# doan2.net
KiCad netlist of a schematic drawn in Altium Designer
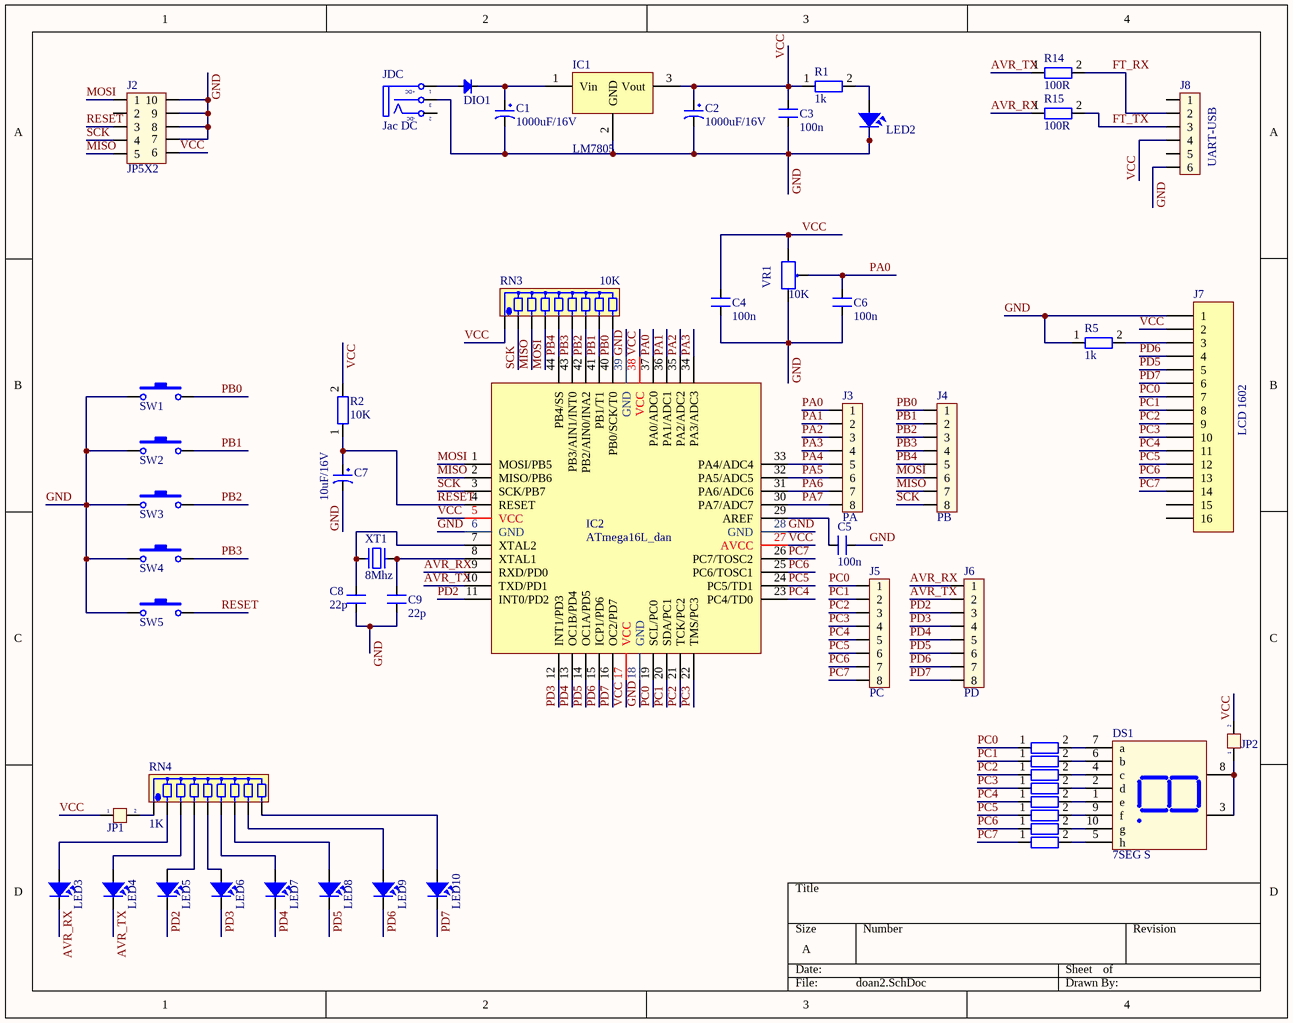
[diagram p0: doan2.SchDoc]

(export (version "E")
  (design (tool "Eeschema 10.0.6"))
  (components
    (comp (ref "C1")
      (value "1000uF/16V")
      (footprint "CAP1000uf/25V")
      (description "Cap 1000uF/16V - 220uF/50V")
      (libsource (lib "doan2") (part "CAP1000uf/25V"))
    )
    (comp (ref "C2")
      (value "1000uF/16V")
      (footprint "CAP1000uf/25V")
      (description "Cap 1000uF/16V - 220uF/50V")
      (libsource (lib "doan2") (part "CAP1000uf/25V"))
    )
    (comp (ref "C3")
      (value "100n")
      (footprint "SM-CAP-0805")
      (fields (field (name "DESIGNED BY") "VanDungEvn"))
      (libsource (lib "doan2") (part "CN"))
    )
    (comp (ref "C4")
      (value "100n")
      (footprint "SM-CAP-0805")
      (fields (field (name "DESIGNED BY") "VanDungEvn"))
      (libsource (lib "doan2") (part "CN"))
    )
    (comp (ref "C5")
      (value "100n")
      (footprint "SM-CAP-0805")
      (fields (field (name "DESIGNED BY") "VanDungEvn"))
      (libsource (lib "doan2") (part "CN"))
    )
    (comp (ref "C6")
      (value "100n")
      (footprint "SM-CAP-0805")
      (fields (field (name "DESIGNED BY") "VanDungEvn"))
      (libsource (lib "doan2") (part "CN"))
    )
    (comp (ref "C7")
      (value "10uF/16V")
      (footprint "CAP10uf/16V")
      (description "Cap 1000uF/16V - 220uF/50V")
      (libsource (lib "doan2") (part "CAP10uf/16V"))
    )
    (comp (ref "C8")
      (value "22p")
      (footprint "SM-CAP-0805")
      (fields (field (name "DESIGNED BY") "VanDungEvn"))
      (libsource (lib "doan2") (part "CN"))
    )
    (comp (ref "C9")
      (value "22p")
      (footprint "SM-CAP-0805")
      (fields (field (name "DESIGNED BY") "VanDungEvn"))
      (libsource (lib "doan2") (part "CN"))
    )
    (comp (ref "DIO1")
      (value "Diode")
      (footprint "DIO-SMD-106")
      (description "Default Diode")
      (fields (field (name "PUBLISHER") "Altium Limited"))
      (libsource (lib "doan2") (part "Diode"))
    )
    (comp (ref "DS1")
      (value "7SEG S")
      (footprint "7SEGS")
      (description "Single 7 Seg Dipslay")
      (libsource (lib "doan2") (part "LED7S"))
    )
    (comp (ref "IC1") (value "LM7805") (footprint "LM7805/DPAK") (libsource (lib "doan2") (part "LM7805")))
    (comp (ref "IC2")
      (value "ATmega16L_dan")
      (footprint "DIP44/W0.6")
      (libsource (lib "doan2") (part "ATmega16L_dan"))
    )
    (comp (ref "J2") (value "JP5X2") (footprint "JP5X2") (libsource (lib "doan2") (part "JP5X2")))
    (comp (ref "J3")
      (value "PA")
      (footprint "JP8")
      (description "JP8 PIN")
      (libsource (lib "doan2") (part "JP8"))
    )
    (comp (ref "J4")
      (value "PB")
      (footprint "JP8")
      (description "JP8 PIN")
      (libsource (lib "doan2") (part "JP8"))
    )
    (comp (ref "J5")
      (value "PC")
      (footprint "JP8")
      (description "JP8 PIN")
      (libsource (lib "doan2") (part "JP8"))
    )
    (comp (ref "J6")
      (value "PD")
      (footprint "JP8")
      (description "JP8 PIN")
      (libsource (lib "doan2") (part "JP8"))
    )
    (comp (ref "J7")
      (value "LCD 1602")
      (footprint "JP16-C1T")
      (description "WR-PHD 2.54 mm Angled Socket Header")
      (fields
        (field (name "MANUFACTURER") "Würth Elektronik eiSos GmbH")
        (field (name "PARTNO") "613016143121")
        (field (name "CREATED BY") "Karrer Zheng")
      )
      (libsource (lib "doan2") (part "JP16"))
    )
    (comp (ref "J8")
      (value "UART-USB")
      (footprint "JP6")
      (description "JP6 PIN")
      (libsource (lib "doan2") (part "JP6"))
    )
    (comp (ref "JDC")
      (value "Jac DC")
      (footprint "DC-IN")
      (description "Jac DC input")
      (libsource (lib "doan2") (part "DCIN"))
    )
    (comp (ref "JP1") (value "Jumper 2") (footprint "JP2") (libsource (lib "doan2") (part "JP 2")))
    (comp (ref "JP2") (value "Jumper 2") (footprint "JP2") (libsource (lib "") (part "JP 2_1")))
    (comp (ref "LED2")
      (value "LED SMD")
      (footprint "SM-LED-0805-Green - duplicate")
      (libsource (lib "doan2") (part "LED-SMD-0805"))
    )
    (comp (ref "LED3")
      (value "LED SMD")
      (footprint "SM-LED-0805-Green - duplicate")
      (libsource (lib "doan2") (part "LED-SMD-0805"))
    )
    (comp (ref "LED4")
      (value "LED SMD")
      (footprint "SM-LED-0805-Green - duplicate")
      (libsource (lib "doan2") (part "LED-SMD-0805"))
    )
    (comp (ref "LED5")
      (value "LED SMD")
      (footprint "SM-LED-0805-Green - duplicate")
      (libsource (lib "doan2") (part "LED-SMD-0805"))
    )
    (comp (ref "LED6")
      (value "LED SMD")
      (footprint "SM-LED-0805-Green - duplicate")
      (libsource (lib "doan2") (part "LED-SMD-0805"))
    )
    (comp (ref "LED7")
      (value "LED SMD")
      (footprint "SM-LED-0805-Green - duplicate")
      (libsource (lib "doan2") (part "LED-SMD-0805"))
    )
    (comp (ref "LED8")
      (value "LED SMD")
      (footprint "SM-LED-0805-Green - duplicate")
      (libsource (lib "doan2") (part "LED-SMD-0805"))
    )
    (comp (ref "LED9")
      (value "LED SMD")
      (footprint "SM-LED-0805-Green - duplicate")
      (libsource (lib "doan2") (part "LED-SMD-0805"))
    )
    (comp (ref "LED10")
      (value "LED SMD")
      (footprint "SM-LED-0805-Green - duplicate")
      (libsource (lib "doan2") (part "LED-SMD-0805"))
    )
    (comp (ref "R1")
      (value "1k")
      (footprint "SM-RES-0805")
      (description "Resistor 1/4W")
      (libsource (lib "doan2") (part "R1/4W"))
    )
    (comp (ref "R2")
      (value "10K")
      (footprint "SM-RES-0805")
      (description "Resistor 1/4W")
      (libsource (lib "doan2") (part "R1/4W"))
    )
    (comp (ref "R5")
      (value "1k")
      (footprint "SM-RES-0805")
      (description "Resistor 1/4W")
      (libsource (lib "doan2") (part "R1/4W"))
    )
    (comp (ref "R6")
      (value "1k")
      (footprint "SM-RES-0805")
      (description "Resistor 1/4W")
      (libsource (lib "doan2") (part "R1/4W"))
    )
    (comp (ref "R7")
      (value "1k")
      (footprint "SM-RES-0805")
      (description "Resistor 1/4W")
      (libsource (lib "doan2") (part "R1/4W"))
    )
    (comp (ref "R8")
      (value "1k")
      (footprint "SM-RES-0805")
      (description "Resistor 1/4W")
      (libsource (lib "doan2") (part "R1/4W"))
    )
    (comp (ref "R9")
      (value "1k")
      (footprint "SM-RES-0805")
      (description "Resistor 1/4W")
      (libsource (lib "doan2") (part "R1/4W"))
    )
    (comp (ref "R10")
      (value "1k")
      (footprint "SM-RES-0805")
      (description "Resistor 1/4W")
      (libsource (lib "doan2") (part "R1/4W"))
    )
    (comp (ref "R11")
      (value "1k")
      (footprint "SM-RES-0805")
      (description "Resistor 1/4W")
      (libsource (lib "doan2") (part "R1/4W"))
    )
    (comp (ref "R12")
      (value "1k")
      (footprint "SM-RES-0805")
      (description "Resistor 1/4W")
      (libsource (lib "doan2") (part "R1/4W"))
    )
    (comp (ref "R13")
      (value "1k")
      (footprint "SM-RES-0805")
      (description "Resistor 1/4W")
      (libsource (lib "doan2") (part "R1/4W"))
    )
    (comp (ref "R14")
      (value "100R")
      (footprint "SM-RES-0805")
      (description "Resistor 1/4W")
      (libsource (lib "doan2") (part "R1/4W"))
    )
    (comp (ref "R15")
      (value "100R")
      (footprint "SM-RES-0805")
      (description "Resistor 1/4W")
      (libsource (lib "doan2") (part "R1/4W"))
    )
    (comp (ref "RN3")
      (value "10K")
      (footprint "RN8")
      (description "Resistor 8 (Thanh)")
      (libsource (lib "doan2") (part "RN8"))
    )
    (comp (ref "RN4")
      (value "1K")
      (footprint "RN8")
      (description "Resistor 8 (Thanh)")
      (libsource (lib "doan2") (part "RN8"))
    )
    (comp (ref "SW1")
      (value "SW-SMD")
      (footprint "SW-SMD")
      (description "Switch")
      (fields (field (name "PUBLISHER") "Altium Limited"))
      (libsource (lib "doan2") (part "SW-SMD"))
    )
    (comp (ref "SW2")
      (value "SW-SMD")
      (footprint "SW-SMD")
      (description "Switch")
      (fields (field (name "PUBLISHER") "Altium Limited"))
      (libsource (lib "doan2") (part "SW-SMD"))
    )
    (comp (ref "SW3")
      (value "SW-SMD")
      (footprint "SW-SMD")
      (description "Switch")
      (fields (field (name "PUBLISHER") "Altium Limited"))
      (libsource (lib "doan2") (part "SW-SMD"))
    )
    (comp (ref "SW4")
      (value "SW-SMD")
      (footprint "SW-SMD")
      (description "Switch")
      (fields (field (name "PUBLISHER") "Altium Limited"))
      (libsource (lib "doan2") (part "SW-SMD"))
    )
    (comp (ref "SW5")
      (value "RESET")
      (footprint "SW-SMD")
      (description "Switch")
      (fields (field (name "PUBLISHER") "Altium Limited"))
      (libsource (lib "doan2") (part "SW-SMD"))
    )
    (comp (ref "VR1")
      (value "10K")
      (footprint "VR")
      (description "Var Resistor")
      (libsource (lib "doan2") (part "VR"))
    )
    (comp (ref "XT1")
      (value "8Mhz")
      (footprint "XT2")
      (description "Crystal For all Crystal 2pin.")
      (libsource (lib "doan2") (part "XT2"))
    )
  )
  (nets
    (net (code "1") (name "/AVR_RX") (class "Default")
      (node (ref "IC2") (pin "9") (pinfunction "RXD/PD0_9") (pintype "passive"))
      (node (ref "J6") (pin "1") (pinfunction "1_1") (pintype "passive"))
      (node (ref "LED3") (pin "2") (pinfunction "2_2") (pintype "passive"))
      (node (ref "R15") (pin "1") (pinfunction "1_1") (pintype "passive"))
    )
    (net (code "2") (name "/AVR_TX") (class "Default")
      (node (ref "IC2") (pin "10") (pinfunction "TXD/PD1_10") (pintype "passive"))
      (node (ref "J6") (pin "2") (pinfunction "2_2") (pintype "passive"))
      (node (ref "LED4") (pin "2") (pinfunction "2_2") (pintype "passive"))
      (node (ref "R14") (pin "1") (pinfunction "1_1") (pintype "passive"))
    )
    (net (code "3") (name "/FT_RX") (class "Default")
      (node (ref "J8") (pin "2") (pinfunction "2_2") (pintype "passive"))
      (node (ref "R14") (pin "2") (pinfunction "2_2") (pintype "passive"))
    )
    (net (code "4") (name "/FT_TX") (class "Default")
      (node (ref "J8") (pin "3") (pinfunction "3_3") (pintype "passive"))
      (node (ref "R15") (pin "2") (pinfunction "2_2") (pintype "passive"))
    )
    (net (code "5") (name "/GND") (class "Default")
      (node (ref "C1") (pin "2") (pinfunction "2_2") (pintype "passive"))
      (node (ref "C2") (pin "2") (pinfunction "2_2") (pintype "passive"))
      (node (ref "C3") (pin "1") (pinfunction "1_1") (pintype "passive"))
      (node (ref "C4") (pin "1") (pinfunction "1_1") (pintype "passive"))
      (node (ref "C5") (pin "1") (pinfunction "1_1") (pintype "passive"))
      (node (ref "C6") (pin "1") (pinfunction "1_1") (pintype "passive"))
      (node (ref "C7") (pin "2") (pinfunction "2_2") (pintype "passive"))
      (node (ref "C8") (pin "1") (pinfunction "1_1") (pintype "passive"))
      (node (ref "C9") (pin "1") (pinfunction "1_1") (pintype "passive"))
      (node (ref "IC1") (pin "2") (pinfunction "GND_2") (pintype "passive"))
      (node (ref "IC2") (pin "18") (pinfunction "GND_18") (pintype "passive"))
      (node (ref "IC2") (pin "28") (pinfunction "GND_28") (pintype "passive"))
      (node (ref "IC2") (pin "39") (pinfunction "GND_39") (pintype "passive"))
      (node (ref "IC2") (pin "6") (pinfunction "GND_6") (pintype "passive"))
      (node (ref "J2") (pin "10") (pinfunction "10_10") (pintype "passive"))
      (node (ref "J2") (pin "7") (pinfunction "7_7") (pintype "passive"))
      (node (ref "J2") (pin "8") (pinfunction "8_8") (pintype "passive"))
      (node (ref "J2") (pin "9") (pinfunction "9_9") (pintype "passive"))
      (node (ref "J7") (pin "1") (pinfunction "1_1") (pintype "passive"))
      (node (ref "J8") (pin "6") (pinfunction "6_6") (pintype "passive"))
      (node (ref "JDC") (pin "3") (pinfunction "S_3") (pintype "power_in"))
      (node (ref "LED2") (pin "2") (pinfunction "2_2") (pintype "passive"))
      (node (ref "R5") (pin "1") (pinfunction "1_1") (pintype "passive"))
      (node (ref "SW1") (pin "1") (pinfunction "1_1") (pintype "passive"))
      (node (ref "SW2") (pin "1") (pinfunction "1_1") (pintype "passive"))
      (node (ref "SW3") (pin "1") (pinfunction "1_1") (pintype "passive"))
      (node (ref "SW4") (pin "1") (pinfunction "1_1") (pintype "passive"))
      (node (ref "SW5") (pin "1") (pinfunction "1_1") (pintype "passive"))
      (node (ref "VR1") (pin "3") (pinfunction "3_3") (pintype "passive"))
    )
    (net (code "6") (name "/MISO") (class "Default")
      (node (ref "IC2") (pin "2") (pinfunction "MISO/PB6_2") (pintype "passive"))
      (node (ref "J2") (pin "5") (pinfunction "5_5") (pintype "passive"))
      (node (ref "J4") (pin "7") (pinfunction "7_7") (pintype "passive"))
      (node (ref "RN3") (pin "3") (pinfunction "3_3") (pintype "passive"))
    )
    (net (code "7") (name "/MOSI") (class "Default")
      (node (ref "IC2") (pin "1") (pinfunction "MOSI/PB5_1") (pintype "passive"))
      (node (ref "J2") (pin "1") (pinfunction "1_1") (pintype "passive"))
      (node (ref "J4") (pin "6") (pinfunction "6_6") (pintype "passive"))
      (node (ref "RN3") (pin "4") (pinfunction "4_4") (pintype "passive"))
    )
    (net (code "8") (name "/PA0") (class "Default")
      (node (ref "C6") (pin "2") (pinfunction "2_2") (pintype "passive"))
      (node (ref "IC2") (pin "37") (pinfunction "PA0/ADC0_37") (pintype "passive"))
      (node (ref "J3") (pin "1") (pinfunction "1_1") (pintype "passive"))
      (node (ref "VR1") (pin "2") (pinfunction "2_2") (pintype "passive"))
    )
    (net (code "9") (name "/PA1") (class "Default")
      (node (ref "IC2") (pin "36") (pinfunction "PA1/ADC1_36") (pintype "passive"))
      (node (ref "J3") (pin "2") (pinfunction "2_2") (pintype "passive"))
    )
    (net (code "10") (name "/PA2") (class "Default")
      (node (ref "IC2") (pin "35") (pinfunction "PA2/ADC2_35") (pintype "passive"))
      (node (ref "J3") (pin "3") (pinfunction "3_3") (pintype "passive"))
    )
    (net (code "11") (name "/PA3") (class "Default")
      (node (ref "IC2") (pin "34") (pinfunction "PA3/ADC3_34") (pintype "passive"))
      (node (ref "J3") (pin "4") (pinfunction "4_4") (pintype "passive"))
    )
    (net (code "12") (name "/PA4") (class "Default")
      (node (ref "IC2") (pin "33") (pinfunction "PA4/ADC4_33") (pintype "passive"))
      (node (ref "J3") (pin "5") (pinfunction "5_5") (pintype "passive"))
    )
    (net (code "13") (name "/PA5") (class "Default")
      (node (ref "IC2") (pin "32") (pinfunction "PA5/ADC5_32") (pintype "passive"))
      (node (ref "J3") (pin "6") (pinfunction "6_6") (pintype "passive"))
    )
    (net (code "14") (name "/PA6") (class "Default")
      (node (ref "IC2") (pin "31") (pinfunction "PA6/ADC6_31") (pintype "passive"))
      (node (ref "J3") (pin "7") (pinfunction "7_7") (pintype "passive"))
    )
    (net (code "15") (name "/PA7") (class "Default")
      (node (ref "IC2") (pin "30") (pinfunction "PA7/ADC7_30") (pintype "passive"))
      (node (ref "J3") (pin "8") (pinfunction "8_8") (pintype "passive"))
    )
    (net (code "16") (name "/PB0") (class "Default")
      (node (ref "IC2") (pin "40") (pinfunction "PB0/SCK/T0_40") (pintype "passive"))
      (node (ref "J4") (pin "1") (pinfunction "1_1") (pintype "passive"))
      (node (ref "RN3") (pin "9") (pinfunction "9_9") (pintype "passive"))
      (node (ref "SW1") (pin "2") (pinfunction "2_2") (pintype "passive"))
    )
    (net (code "17") (name "/PB1") (class "Default")
      (node (ref "IC2") (pin "41") (pinfunction "PB1/T1_41") (pintype "passive"))
      (node (ref "J4") (pin "2") (pinfunction "2_2") (pintype "passive"))
      (node (ref "RN3") (pin "8") (pinfunction "8_8") (pintype "passive"))
      (node (ref "SW2") (pin "2") (pinfunction "2_2") (pintype "passive"))
    )
    (net (code "18") (name "/PB2") (class "Default")
      (node (ref "IC2") (pin "42") (pinfunction "PB2/AIN0/INA2_42") (pintype "passive"))
      (node (ref "J4") (pin "3") (pinfunction "3_3") (pintype "passive"))
      (node (ref "RN3") (pin "7") (pinfunction "7_7") (pintype "passive"))
      (node (ref "SW3") (pin "2") (pinfunction "2_2") (pintype "passive"))
    )
    (net (code "19") (name "/PB3") (class "Default")
      (node (ref "IC2") (pin "43") (pinfunction "PB3/AIN1/INT0_43") (pintype "passive"))
      (node (ref "J4") (pin "4") (pinfunction "4_4") (pintype "passive"))
      (node (ref "RN3") (pin "6") (pinfunction "6_6") (pintype "passive"))
      (node (ref "SW4") (pin "2") (pinfunction "2_2") (pintype "passive"))
    )
    (net (code "20") (name "/PB4") (class "Default")
      (node (ref "IC2") (pin "44") (pinfunction "PB4/SS_44") (pintype "passive"))
      (node (ref "J4") (pin "5") (pinfunction "5_5") (pintype "passive"))
      (node (ref "RN3") (pin "5") (pinfunction "5_5") (pintype "passive"))
    )
    (net (code "21") (name "/PC0") (class "Default")
      (node (ref "IC2") (pin "19") (pinfunction "SCL/PC0_19") (pintype "passive"))
      (node (ref "J5") (pin "1") (pinfunction "1_1") (pintype "passive"))
      (node (ref "J7") (pin "7") (pinfunction "7_7") (pintype "passive"))
      (node (ref "R6") (pin "1") (pinfunction "1_1") (pintype "passive"))
    )
    (net (code "22") (name "/PC1") (class "Default")
      (node (ref "IC2") (pin "20") (pinfunction "SDA/PC1_20") (pintype "passive"))
      (node (ref "J5") (pin "2") (pinfunction "2_2") (pintype "passive"))
      (node (ref "J7") (pin "8") (pinfunction "8_8") (pintype "passive"))
      (node (ref "R7") (pin "1") (pinfunction "1_1") (pintype "passive"))
    )
    (net (code "23") (name "/PC2") (class "Default")
      (node (ref "IC2") (pin "21") (pinfunction "TCK/PC2_21") (pintype "passive"))
      (node (ref "J5") (pin "3") (pinfunction "3_3") (pintype "passive"))
      (node (ref "J7") (pin "9") (pinfunction "9_9") (pintype "passive"))
      (node (ref "R8") (pin "1") (pinfunction "1_1") (pintype "passive"))
    )
    (net (code "24") (name "/PC3") (class "Default")
      (node (ref "IC2") (pin "22") (pinfunction "TMS/PC3_22") (pintype "passive"))
      (node (ref "J5") (pin "4") (pinfunction "4_4") (pintype "passive"))
      (node (ref "J7") (pin "10") (pinfunction "10_10") (pintype "passive"))
      (node (ref "R9") (pin "1") (pinfunction "1_1") (pintype "passive"))
    )
    (net (code "25") (name "/PC4") (class "Default")
      (node (ref "IC2") (pin "23") (pinfunction "PC4/TD0_23") (pintype "passive"))
      (node (ref "J5") (pin "5") (pinfunction "5_5") (pintype "passive"))
      (node (ref "J7") (pin "11") (pinfunction "11_11") (pintype "passive"))
      (node (ref "R10") (pin "1") (pinfunction "1_1") (pintype "passive"))
    )
    (net (code "26") (name "/PC5") (class "Default")
      (node (ref "IC2") (pin "24") (pinfunction "PC5/TD1_24") (pintype "passive"))
      (node (ref "J5") (pin "6") (pinfunction "6_6") (pintype "passive"))
      (node (ref "J7") (pin "12") (pinfunction "12_12") (pintype "passive"))
      (node (ref "R11") (pin "1") (pinfunction "1_1") (pintype "passive"))
    )
    (net (code "27") (name "/PC6") (class "Default")
      (node (ref "IC2") (pin "25") (pinfunction "PC6/TOSC1_25") (pintype "passive"))
      (node (ref "J5") (pin "7") (pinfunction "7_7") (pintype "passive"))
      (node (ref "J7") (pin "13") (pinfunction "13_13") (pintype "passive"))
      (node (ref "R12") (pin "1") (pinfunction "1_1") (pintype "passive"))
    )
    (net (code "28") (name "/PC7") (class "Default")
      (node (ref "IC2") (pin "26") (pinfunction "PC7/TOSC2_26") (pintype "passive"))
      (node (ref "J5") (pin "8") (pinfunction "8_8") (pintype "passive"))
      (node (ref "J7") (pin "14") (pinfunction "14_14") (pintype "passive"))
      (node (ref "R13") (pin "1") (pinfunction "1_1") (pintype "passive"))
    )
    (net (code "29") (name "/PD2") (class "Default")
      (node (ref "IC2") (pin "11") (pinfunction "INT0/PD2_11") (pintype "passive"))
      (node (ref "J6") (pin "3") (pinfunction "3_3") (pintype "passive"))
      (node (ref "LED5") (pin "2") (pinfunction "2_2") (pintype "passive"))
    )
    (net (code "30") (name "/PD3") (class "Default")
      (node (ref "IC2") (pin "12") (pinfunction "INT1/PD3_12") (pintype "passive"))
      (node (ref "J6") (pin "4") (pinfunction "4_4") (pintype "passive"))
      (node (ref "LED6") (pin "2") (pinfunction "2_2") (pintype "passive"))
    )
    (net (code "31") (name "/PD4") (class "Default")
      (node (ref "IC2") (pin "13") (pinfunction "OC1B/PD4_13") (pintype "passive"))
      (node (ref "J6") (pin "5") (pinfunction "5_5") (pintype "passive"))
      (node (ref "LED7") (pin "2") (pinfunction "2_2") (pintype "passive"))
    )
    (net (code "32") (name "/PD5") (class "Default")
      (node (ref "IC2") (pin "14") (pinfunction "OC1A/PD5_14") (pintype "passive"))
      (node (ref "J6") (pin "6") (pinfunction "6_6") (pintype "passive"))
      (node (ref "J7") (pin "5") (pinfunction "5_5") (pintype "passive"))
      (node (ref "LED8") (pin "2") (pinfunction "2_2") (pintype "passive"))
    )
    (net (code "33") (name "/PD6") (class "Default")
      (node (ref "IC2") (pin "15") (pinfunction "ICP1/PD6_15") (pintype "passive"))
      (node (ref "J6") (pin "7") (pinfunction "7_7") (pintype "passive"))
      (node (ref "J7") (pin "4") (pinfunction "4_4") (pintype "passive"))
      (node (ref "LED9") (pin "2") (pinfunction "2_2") (pintype "passive"))
    )
    (net (code "34") (name "/PD7") (class "Default")
      (node (ref "IC2") (pin "16") (pinfunction "OC2/PD7_16") (pintype "passive"))
      (node (ref "J6") (pin "8") (pinfunction "8_8") (pintype "passive"))
      (node (ref "J7") (pin "6") (pinfunction "6_6") (pintype "passive"))
      (node (ref "LED10") (pin "2") (pinfunction "2_2") (pintype "passive"))
    )
    (net (code "35") (name "/RESET") (class "Default")
      (node (ref "C7") (pin "1") (pinfunction "1_1") (pintype "passive"))
      (node (ref "IC2") (pin "4") (pinfunction "RESET_4") (pintype "passive"))
      (node (ref "J2") (pin "3") (pinfunction "3_3") (pintype "passive"))
      (node (ref "R2") (pin "1") (pinfunction "1_1") (pintype "passive"))
      (node (ref "SW5") (pin "2") (pinfunction "2_2") (pintype "passive"))
    )
    (net (code "36") (name "/SCK") (class "Default")
      (node (ref "IC2") (pin "3") (pinfunction "SCK/PB7_3") (pintype "passive"))
      (node (ref "J2") (pin "4") (pinfunction "4_4") (pintype "passive"))
      (node (ref "J4") (pin "8") (pinfunction "8_8") (pintype "passive"))
      (node (ref "RN3") (pin "2") (pinfunction "2_2") (pintype "passive"))
    )
    (net (code "37") (name "/VCC") (class "Default")
      (node (ref "C2") (pin "1") (pinfunction "1_1") (pintype "passive"))
      (node (ref "C3") (pin "2") (pinfunction "2_2") (pintype "passive"))
      (node (ref "C4") (pin "2") (pinfunction "2_2") (pintype "passive"))
      (node (ref "IC1") (pin "3") (pinfunction "Vout_3") (pintype "passive"))
      (node (ref "IC2") (pin "17") (pinfunction "VCC_17") (pintype "passive"))
      (node (ref "IC2") (pin "27") (pinfunction "AVCC_27") (pintype "passive"))
      (node (ref "IC2") (pin "38") (pinfunction "VCC_38") (pintype "passive"))
      (node (ref "IC2") (pin "5") (pinfunction "VCC_5") (pintype "passive"))
      (node (ref "J2") (pin "6") (pinfunction "6_6") (pintype "passive"))
      (node (ref "J7") (pin "2") (pinfunction "2_2") (pintype "passive"))
      (node (ref "J8") (pin "4") (pinfunction "4_4") (pintype "passive"))
      (node (ref "JP1") (pin "1") (pinfunction "1_1") (pintype "passive"))
      (node (ref "JP2") (pin "2") (pinfunction "2_2") (pintype "passive"))
      (node (ref "R1") (pin "1") (pinfunction "1_1") (pintype "passive"))
      (node (ref "R2") (pin "2") (pinfunction "2_2") (pintype "passive"))
      (node (ref "RN3") (pin "1") (pinfunction "1_1") (pintype "passive"))
      (node (ref "VR1") (pin "1") (pinfunction "1_1") (pintype "passive"))
    )
    (net (code "38") (name "Net-(DIO1-A)") (class "Default")
      (node (ref "DIO1") (pin "1") (pinfunction "A_1") (pintype "passive"))
      (node (ref "JDC") (pin "1") (pinfunction "T_1") (pintype "passive"))
    )
    (net (code "39") (name "Net-(DIO1-K)") (class "Default")
      (node (ref "C1") (pin "1") (pinfunction "1_1") (pintype "passive"))
      (node (ref "DIO1") (pin "2") (pinfunction "K_2") (pintype "passive"))
      (node (ref "IC1") (pin "1") (pinfunction "Vin_1") (pintype "passive"))
    )
    (net (code "40") (name "Net-(DS1-Vcc-Pad3)") (class "Default")
      (node (ref "DS1") (pin "3") (pinfunction "Vcc_3") (pintype "passive"))
      (node (ref "DS1") (pin "8") (pinfunction "Vcc_8") (pintype "passive"))
      (node (ref "JP2") (pin "1") (pinfunction "1_1") (pintype "passive"))
    )
    (net (code "41") (name "Net-(DS1-a)") (class "Default")
      (node (ref "DS1") (pin "7") (pinfunction "a_7") (pintype "passive"))
      (node (ref "R6") (pin "2") (pinfunction "2_2") (pintype "passive"))
    )
    (net (code "42") (name "Net-(DS1-b)") (class "Default")
      (node (ref "DS1") (pin "6") (pinfunction "b_6") (pintype "passive"))
      (node (ref "R7") (pin "2") (pinfunction "2_2") (pintype "passive"))
    )
    (net (code "43") (name "Net-(DS1-c)") (class "Default")
      (node (ref "DS1") (pin "4") (pinfunction "c_4") (pintype "passive"))
      (node (ref "R8") (pin "2") (pinfunction "2_2") (pintype "passive"))
    )
    (net (code "44") (name "Net-(DS1-d)") (class "Default")
      (node (ref "DS1") (pin "2") (pinfunction "d_2") (pintype "passive"))
      (node (ref "R9") (pin "2") (pinfunction "2_2") (pintype "passive"))
    )
    (net (code "45") (name "Net-(DS1-e)") (class "Default")
      (node (ref "DS1") (pin "1") (pinfunction "e_1") (pintype "passive"))
      (node (ref "R10") (pin "2") (pinfunction "2_2") (pintype "passive"))
    )
    (net (code "46") (name "Net-(DS1-f)") (class "Default")
      (node (ref "DS1") (pin "9") (pinfunction "f_9") (pintype "passive"))
      (node (ref "R11") (pin "2") (pinfunction "2_2") (pintype "passive"))
    )
    (net (code "47") (name "Net-(DS1-g)") (class "Default")
      (node (ref "DS1") (pin "10") (pinfunction "g_10") (pintype "passive"))
      (node (ref "R12") (pin "2") (pinfunction "2_2") (pintype "passive"))
    )
    (net (code "48") (name "Net-(DS1-h)") (class "Default")
      (node (ref "DS1") (pin "5") (pinfunction "h_5") (pintype "passive"))
      (node (ref "R13") (pin "2") (pinfunction "2_2") (pintype "passive"))
    )
    (net (code "49") (name "Net-(IC2-AREF)") (class "Default")
      (node (ref "C5") (pin "2") (pinfunction "2_2") (pintype "passive"))
      (node (ref "IC2") (pin "29") (pinfunction "AREF_29") (pintype "passive"))
    )
    (net (code "50") (name "Net-(IC2-XTAL1)") (class "Default")
      (node (ref "C9") (pin "2") (pinfunction "2_2") (pintype "passive"))
      (node (ref "IC2") (pin "8") (pinfunction "XTAL1_8") (pintype "passive"))
      (node (ref "XT1") (pin "1") (pinfunction "1_1") (pintype "passive"))
    )
    (net (code "51") (name "Net-(IC2-XTAL2)") (class "Default")
      (node (ref "C8") (pin "2") (pinfunction "2_2") (pintype "passive"))
      (node (ref "IC2") (pin "7") (pinfunction "XTAL2_7") (pintype "passive"))
      (node (ref "XT1") (pin "2") (pinfunction "2_2") (pintype "passive"))
    )
    (net (code "52") (name "Net-(J7-Pad3)") (class "Default")
      (node (ref "J7") (pin "3") (pinfunction "3_3") (pintype "passive"))
      (node (ref "R5") (pin "2") (pinfunction "2_2") (pintype "passive"))
    )
    (net (code "53") (name "Net-(JP1-Pad2)") (class "Default")
      (node (ref "JP1") (pin "2") (pinfunction "2_2") (pintype "passive"))
      (node (ref "RN4") (pin "1") (pinfunction "1_1") (pintype "passive"))
    )
    (net (code "54") (name "Net-(LED2-Pad1)") (class "Default")
      (node (ref "LED2") (pin "1") (pinfunction "1_1") (pintype "passive"))
      (node (ref "R1") (pin "2") (pinfunction "2_2") (pintype "passive"))
    )
    (net (code "55") (name "Net-(LED3-Pad1)") (class "Default")
      (node (ref "LED3") (pin "1") (pinfunction "1_1") (pintype "passive"))
      (node (ref "RN4") (pin "2") (pinfunction "2_2") (pintype "passive"))
    )
    (net (code "56") (name "Net-(LED4-Pad1)") (class "Default")
      (node (ref "LED4") (pin "1") (pinfunction "1_1") (pintype "passive"))
      (node (ref "RN4") (pin "3") (pinfunction "3_3") (pintype "passive"))
    )
    (net (code "57") (name "Net-(LED5-Pad1)") (class "Default")
      (node (ref "LED5") (pin "1") (pinfunction "1_1") (pintype "passive"))
      (node (ref "RN4") (pin "4") (pinfunction "4_4") (pintype "passive"))
    )
    (net (code "58") (name "Net-(LED6-Pad1)") (class "Default")
      (node (ref "LED6") (pin "1") (pinfunction "1_1") (pintype "passive"))
      (node (ref "RN4") (pin "5") (pinfunction "5_5") (pintype "passive"))
    )
    (net (code "59") (name "Net-(LED7-Pad1)") (class "Default")
      (node (ref "LED7") (pin "1") (pinfunction "1_1") (pintype "passive"))
      (node (ref "RN4") (pin "6") (pinfunction "6_6") (pintype "passive"))
    )
    (net (code "60") (name "Net-(LED8-Pad1)") (class "Default")
      (node (ref "LED8") (pin "1") (pinfunction "1_1") (pintype "passive"))
      (node (ref "RN4") (pin "7") (pinfunction "7_7") (pintype "passive"))
    )
    (net (code "61") (name "Net-(LED9-Pad1)") (class "Default")
      (node (ref "LED9") (pin "1") (pinfunction "1_1") (pintype "passive"))
      (node (ref "RN4") (pin "8") (pinfunction "8_8") (pintype "passive"))
    )
    (net (code "62") (name "Net-(LED10-Pad1)") (class "Default")
      (node (ref "LED10") (pin "1") (pinfunction "1_1") (pintype "passive"))
      (node (ref "RN4") (pin "9") (pinfunction "9_9") (pintype "passive"))
    )
    (net (code "63") (name "unconnected-(J2-Pad2)") (class "Default")
      (node (ref "J2") (pin "2") (pinfunction "2_2") (pintype "passive"))
    )
    (net (code "64") (name "unconnected-(J7-Pad15)") (class "Default")
      (node (ref "J7") (pin "15") (pinfunction "15_15") (pintype "passive"))
    )
    (net (code "65") (name "unconnected-(J7-Pad16)") (class "Default")
      (node (ref "J7") (pin "16") (pinfunction "16_16") (pintype "passive"))
    )
    (net (code "66") (name "unconnected-(J8-Pad1)") (class "Default")
      (node (ref "J8") (pin "1") (pinfunction "1_1") (pintype "passive"))
    )
    (net (code "67") (name "unconnected-(J8-Pad5)") (class "Default")
      (node (ref "J8") (pin "5") (pinfunction "5_5") (pintype "passive"))
    )
    (net (code "68") (name "unconnected-(JDC-TN-Pad2)") (class "Default")
      (node (ref "JDC") (pin "2") (pinfunction "TN_2") (pintype "passive"))
    )
  )
)
